# Macropadmod.net
KiCad netlist of a schematic drawn in Altium Designer
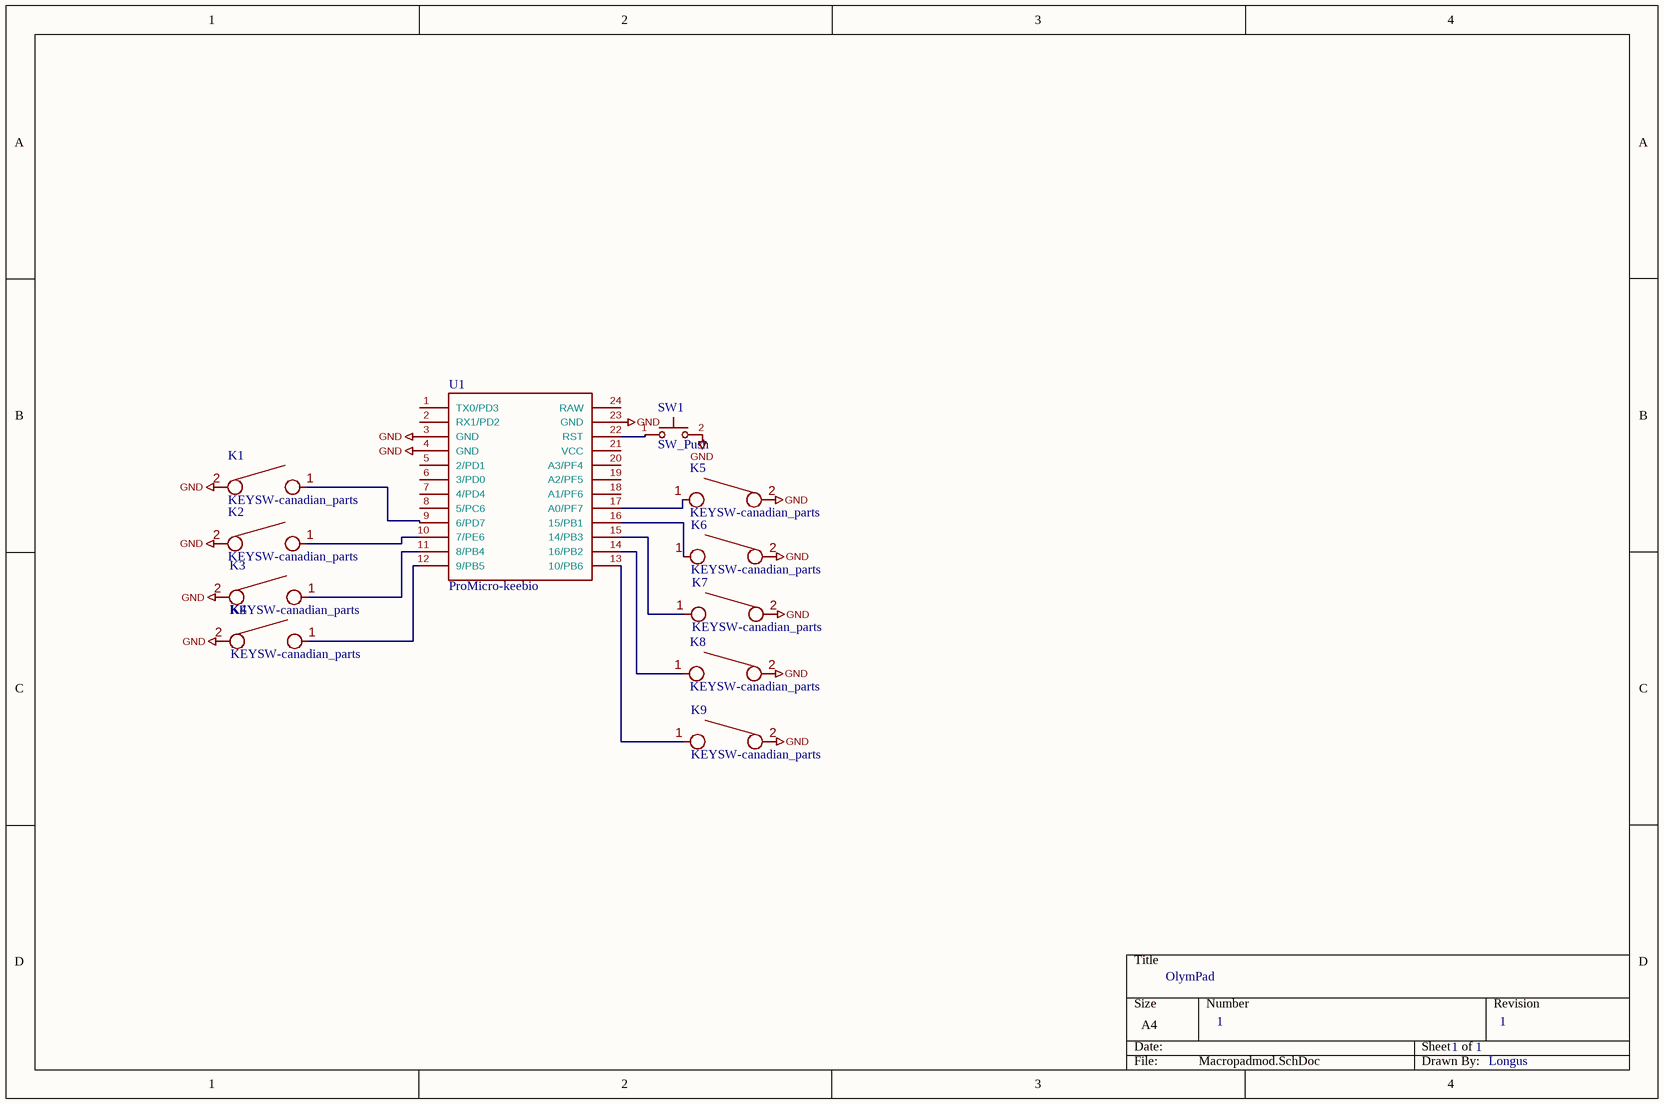
[diagram p0: Macropadmod.SchDoc]

(export (version "E")
  (design (tool "Eeschema 10.0.6"))
  (components
    (comp (ref "K1")
      (value "KEYSW-canadian_parts")
      (footprint "Socket")
      (libsource (lib "Macropad") (part "KEYSW-canadian_parts"))
    )
    (comp (ref "K2")
      (value "KEYSW-canadian_parts")
      (footprint "Socket")
      (libsource (lib "Macropad") (part "KEYSW-canadian_parts"))
    )
    (comp (ref "K3")
      (value "KEYSW-canadian_parts")
      (footprint "Socket")
      (libsource (lib "Macropad") (part "KEYSW-canadian_parts"))
    )
    (comp (ref "K4")
      (value "KEYSW-canadian_parts")
      (footprint "Socket")
      (libsource (lib "Macropad") (part "KEYSW-canadian_parts"))
    )
    (comp (ref "K5")
      (value "KEYSW-canadian_parts")
      (footprint "Socket")
      (libsource (lib "Macropad") (part "KEYSW-canadian_parts"))
    )
    (comp (ref "K6")
      (value "KEYSW-canadian_parts")
      (footprint "Socket")
      (libsource (lib "Macropad") (part "KEYSW-canadian_parts"))
    )
    (comp (ref "K7")
      (value "KEYSW-canadian_parts")
      (footprint "Socket")
      (libsource (lib "Macropad") (part "KEYSW-canadian_parts"))
    )
    (comp (ref "K8")
      (value "KEYSW-canadian_parts")
      (footprint "Socket")
      (libsource (lib "Macropad") (part "KEYSW-canadian_parts"))
    )
    (comp (ref "K9")
      (value "KEYSW-canadian_parts")
      (footprint "Socket")
      (libsource (lib "Macropad") (part "KEYSW-canadian_parts"))
    )
    (comp (ref "SW1") (value "SW_Push") (footprint "Reset") (libsource (lib "Macropad") (part "SW_Push")))
    (comp (ref "U1")
      (value "ProMicro-keebio")
      (footprint "Pro-Micro")
      (libsource (lib "Macropad") (part "ProMicro-keebio"))
    )
  )
  (nets
    (net (code "1") (name "GND") (class "Default")
      (node (ref "K1") (pin "2") (pinfunction "2_2") (pintype "passive"))
      (node (ref "K2") (pin "2") (pinfunction "2_2") (pintype "passive"))
      (node (ref "K3") (pin "2") (pinfunction "2_2") (pintype "passive"))
      (node (ref "K4") (pin "2") (pinfunction "2_2") (pintype "passive"))
      (node (ref "K5") (pin "2") (pinfunction "2_2") (pintype "passive"))
      (node (ref "K6") (pin "2") (pinfunction "2_2") (pintype "passive"))
      (node (ref "K7") (pin "2") (pinfunction "2_2") (pintype "passive"))
      (node (ref "K8") (pin "2") (pinfunction "2_2") (pintype "passive"))
      (node (ref "K9") (pin "2") (pinfunction "2_2") (pintype "passive"))
      (node (ref "SW1") (pin "2") (pinfunction "2_2") (pintype "passive"))
      (node (ref "U1") (pin "23") (pinfunction "GND_23") (pintype "passive"))
      (node (ref "U1") (pin "3") (pinfunction "GND_3") (pintype "passive"))
      (node (ref "U1") (pin "4") (pinfunction "GND_4") (pintype "passive"))
    )
    (net (code "2") (name "Net-(U1-6{slash}PD7)") (class "Default")
      (node (ref "K1") (pin "1") (pinfunction "1_1") (pintype "passive"))
      (node (ref "U1") (pin "9") (pinfunction "6/PD7_9") (pintype "passive"))
    )
    (net (code "3") (name "Net-(U1-7{slash}PE6)") (class "Default")
      (node (ref "K2") (pin "1") (pinfunction "1_1") (pintype "passive"))
      (node (ref "U1") (pin "10") (pinfunction "7/PE6_10") (pintype "passive"))
    )
    (net (code "4") (name "Net-(U1-8{slash}PB4)") (class "Default")
      (node (ref "K3") (pin "1") (pinfunction "1_1") (pintype "passive"))
      (node (ref "U1") (pin "11") (pinfunction "8/PB4_11") (pintype "passive"))
    )
    (net (code "5") (name "Net-(U1-9{slash}PB5)") (class "Default")
      (node (ref "K4") (pin "1") (pinfunction "1_1") (pintype "passive"))
      (node (ref "U1") (pin "12") (pinfunction "9/PB5_12") (pintype "passive"))
    )
    (net (code "6") (name "Net-(U1-10{slash}PB6)") (class "Default")
      (node (ref "K9") (pin "1") (pinfunction "1_1") (pintype "passive"))
      (node (ref "U1") (pin "13") (pinfunction "10/PB6_13") (pintype "passive"))
    )
    (net (code "7") (name "Net-(U1-14{slash}PB3)") (class "Default")
      (node (ref "K7") (pin "1") (pinfunction "1_1") (pintype "passive"))
      (node (ref "U1") (pin "15") (pinfunction "14/PB3_15") (pintype "passive"))
    )
    (net (code "8") (name "Net-(U1-15{slash}PB1)") (class "Default")
      (node (ref "K6") (pin "1") (pinfunction "1_1") (pintype "passive"))
      (node (ref "U1") (pin "16") (pinfunction "15/PB1_16") (pintype "passive"))
    )
    (net (code "9") (name "Net-(U1-16{slash}PB2)") (class "Default")
      (node (ref "K8") (pin "1") (pinfunction "1_1") (pintype "passive"))
      (node (ref "U1") (pin "14") (pinfunction "16/PB2_14") (pintype "passive"))
    )
    (net (code "10") (name "Net-(U1-A0{slash}PF7)") (class "Default")
      (node (ref "K5") (pin "1") (pinfunction "1_1") (pintype "passive"))
      (node (ref "U1") (pin "17") (pinfunction "A0/PF7_17") (pintype "passive"))
    )
    (net (code "11") (name "Net-(U1-RST)") (class "Default")
      (node (ref "SW1") (pin "1") (pinfunction "1_1") (pintype "passive"))
      (node (ref "U1") (pin "22") (pinfunction "RST_22") (pintype "passive"))
    )
    (net (code "12") (name "unconnected-(U1-2{slash}PD1-Pad5)") (class "Default")
      (node (ref "U1") (pin "5") (pinfunction "2/PD1_5") (pintype "passive"))
    )
    (net (code "13") (name "unconnected-(U1-3{slash}PD0-Pad6)") (class "Default")
      (node (ref "U1") (pin "6") (pinfunction "3/PD0_6") (pintype "passive"))
    )
    (net (code "14") (name "unconnected-(U1-4{slash}PD4-Pad7)") (class "Default")
      (node (ref "U1") (pin "7") (pinfunction "4/PD4_7") (pintype "passive"))
    )
    (net (code "15") (name "unconnected-(U1-5{slash}PC6-Pad8)") (class "Default")
      (node (ref "U1") (pin "8") (pinfunction "5/PC6_8") (pintype "passive"))
    )
    (net (code "16") (name "unconnected-(U1-A1{slash}PF6-Pad18)") (class "Default")
      (node (ref "U1") (pin "18") (pinfunction "A1/PF6_18") (pintype "passive"))
    )
    (net (code "17") (name "unconnected-(U1-A2{slash}PF5-Pad19)") (class "Default")
      (node (ref "U1") (pin "19") (pinfunction "A2/PF5_19") (pintype "passive"))
    )
    (net (code "18") (name "unconnected-(U1-A3{slash}PF4-Pad20)") (class "Default")
      (node (ref "U1") (pin "20") (pinfunction "A3/PF4_20") (pintype "passive"))
    )
    (net (code "19") (name "unconnected-(U1-RAW-Pad24)") (class "Default")
      (node (ref "U1") (pin "24") (pinfunction "RAW_24") (pintype "passive"))
    )
    (net (code "20") (name "unconnected-(U1-RX1{slash}PD2-Pad2)") (class "Default")
      (node (ref "U1") (pin "2") (pinfunction "RX1/PD2_2") (pintype "passive"))
    )
    (net (code "21") (name "unconnected-(U1-TX0{slash}PD3-Pad1)") (class "Default")
      (node (ref "U1") (pin "1") (pinfunction "TX0/PD3_1") (pintype "passive"))
    )
    (net (code "22") (name "unconnected-(U1-VCC-Pad21)") (class "Default")
      (node (ref "U1") (pin "21") (pinfunction "VCC_21") (pintype "passive"))
    )
  )
)
